# KA2_2.net
KiCad netlist of a schematic drawn in Altium Designer
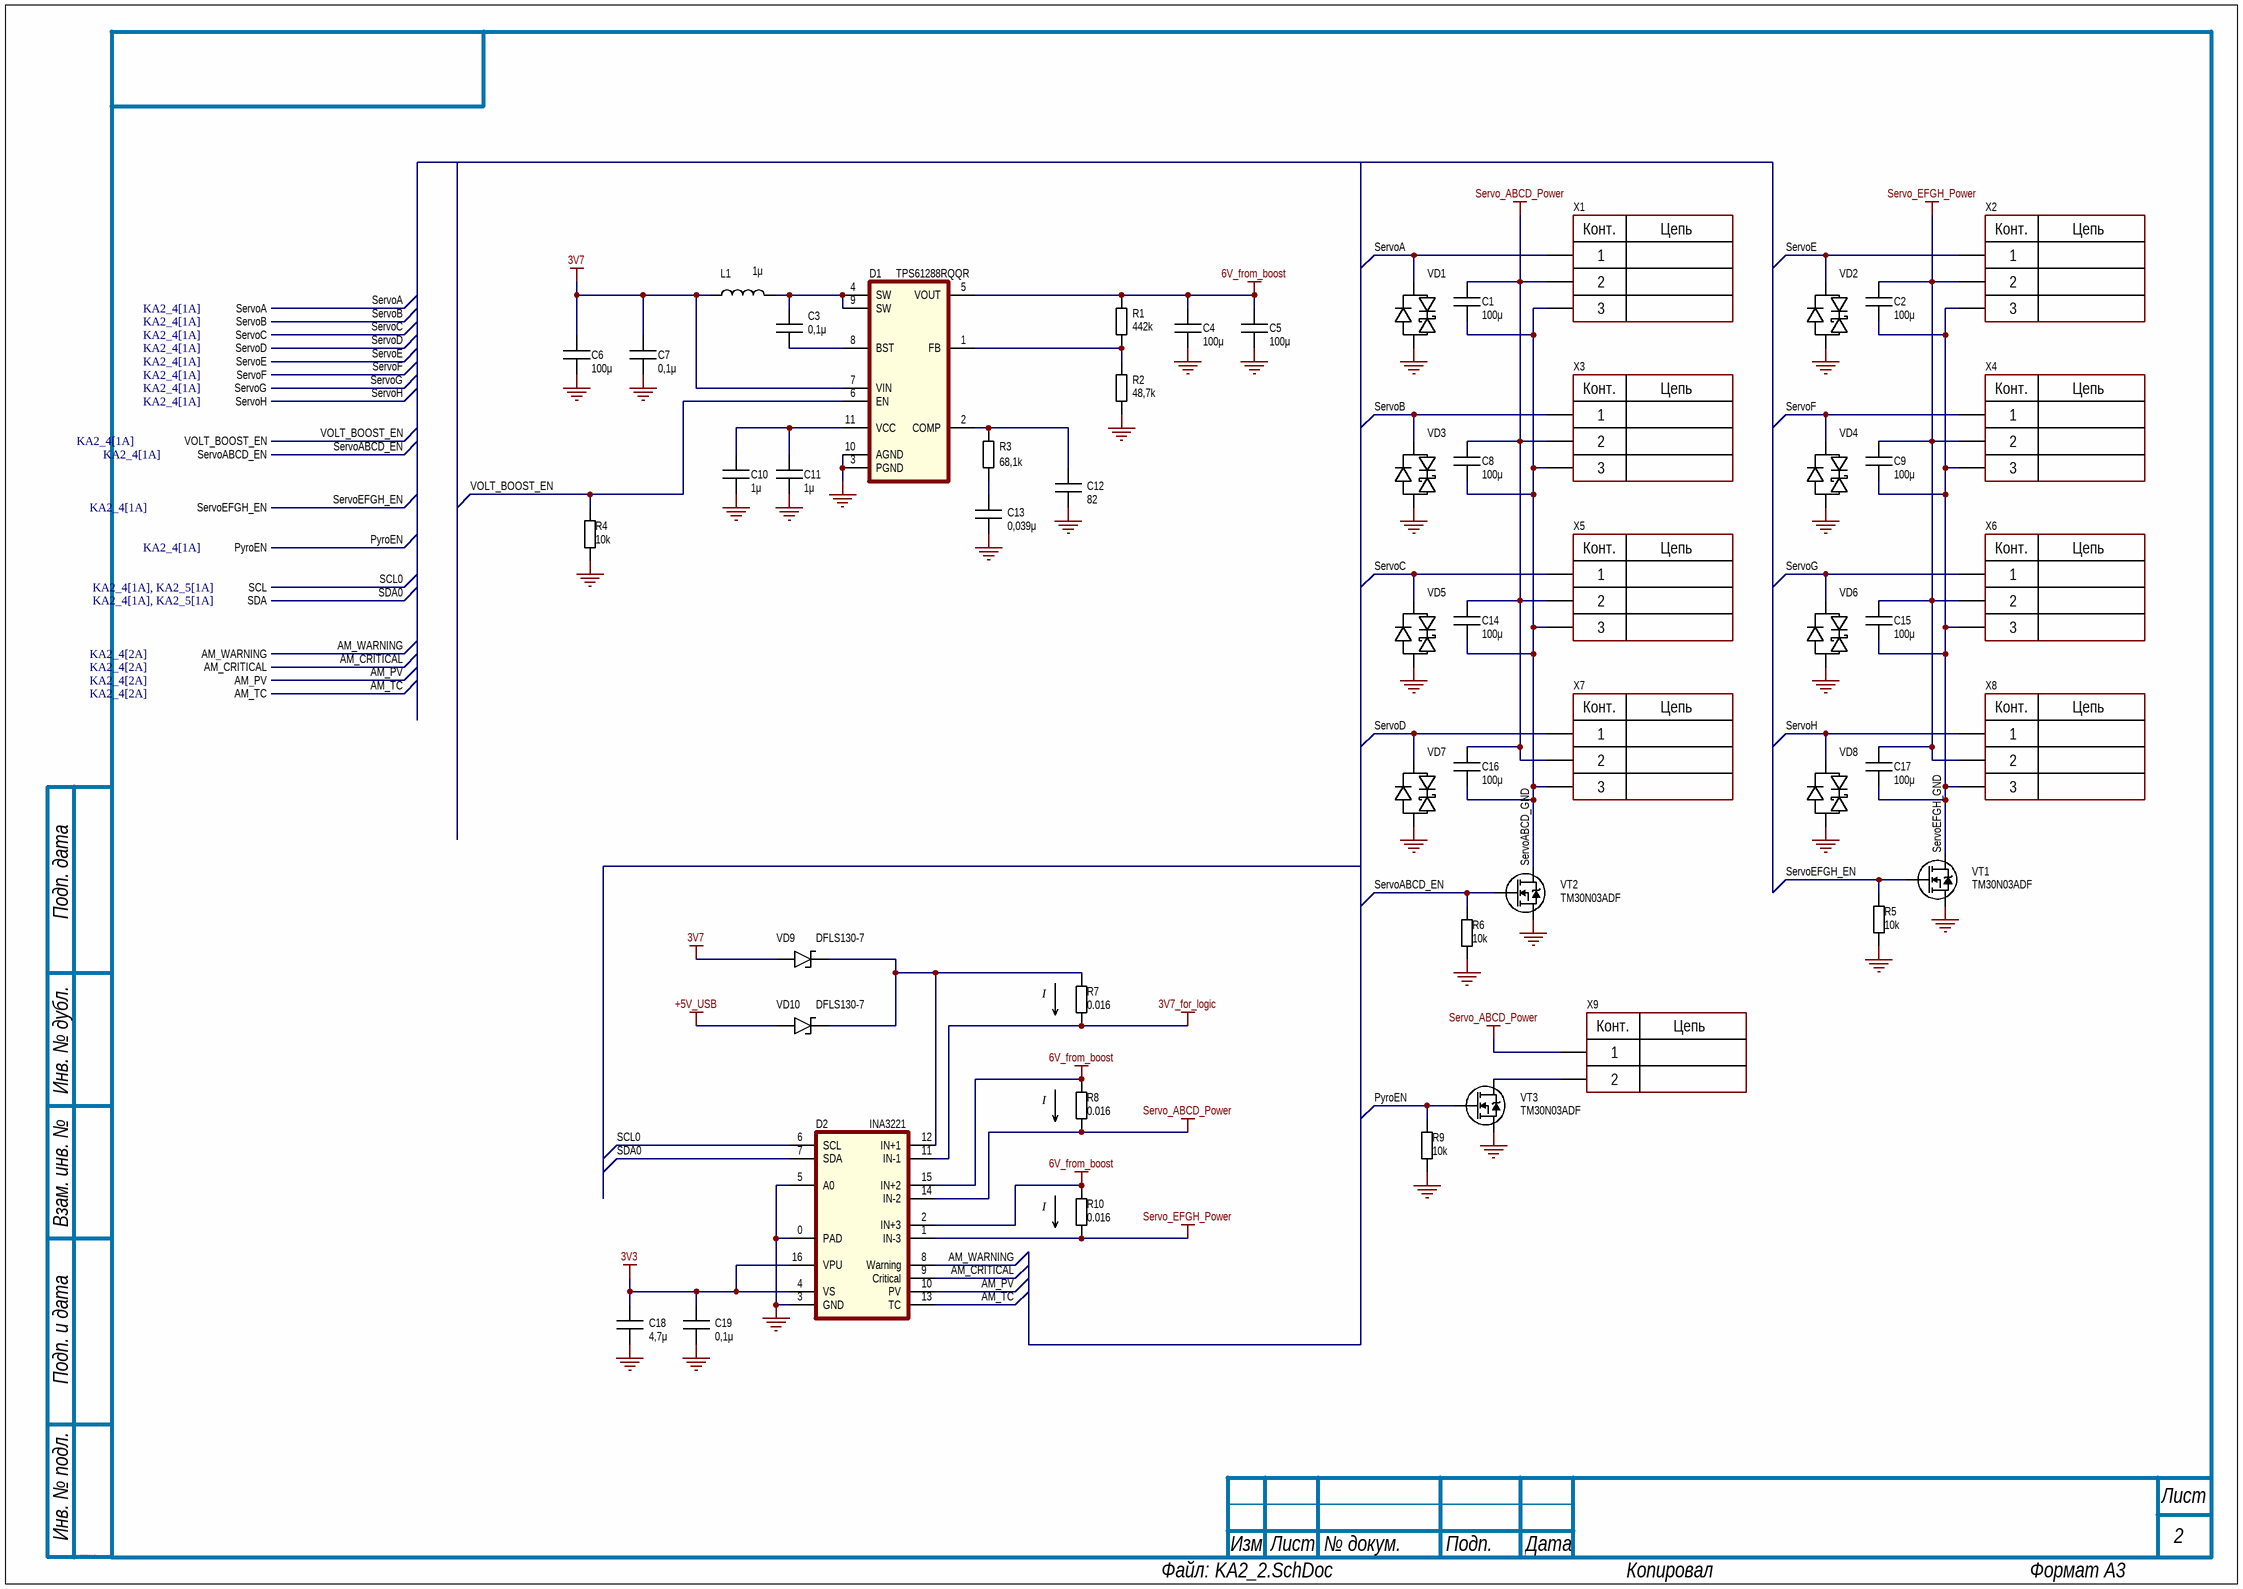
[diagram p0: KA2_2.SchDoc]

(export (version "E")
  (design (tool "Eeschema 10.0.6"))
  (components
    (comp (ref "C1")
      (value "100μ")
      (footprint "Capacitor_1206")
      (fields
        (field (name "VALUEMANUFACTURERPARTNUMBER") "Ceramic capacitor, 100μ, X7R, ±10%, 50V, 1206")
        (field (name "TOLERANCE") "±10%")
        (field (name "VOLTAGE") "50V")
      )
      (libsource (lib "Barsotion") (part "Ceramic_1206"))
    )
    (comp (ref "C2")
      (value "100μ")
      (footprint "Capacitor_1206")
      (fields
        (field (name "VALUEMANUFACTURERPARTNUMBER") "Ceramic capacitor, 100μ, X7R, ±10%, 50V, 1206")
        (field (name "TOLERANCE") "±10%")
        (field (name "VOLTAGE") "50V")
      )
      (libsource (lib "Barsotion") (part "Ceramic_1206"))
    )
    (comp (ref "C3")
      (value "0,1μ")
      (footprint "Capacitor_0402")
      (fields
        (field (name "VALUEMANUFACTURERPARTNUMBER") "Ceramic capacitor, 0,1μ, X7R, ±10%, 16V, 0402")
        (field (name "TOLERANCE") "±10%")
        (field (name "VOLTAGE") "16V")
      )
      (libsource (lib "Barsotion") (part "Ceramic_0402"))
    )
    (comp (ref "C4")
      (value "100μ")
      (footprint "Capacitor_1206")
      (fields
        (field (name "VALUEMANUFACTURERPARTNUMBER") "Ceramic capacitor, 100μ, X7R, ±10%, 50V, 1206")
        (field (name "TOLERANCE") "±10%")
        (field (name "VOLTAGE") "50V")
      )
      (libsource (lib "Barsotion") (part "Ceramic_1206"))
    )
    (comp (ref "C5")
      (value "100μ")
      (footprint "Capacitor_1206")
      (fields
        (field (name "VALUEMANUFACTURERPARTNUMBER") "Ceramic capacitor, 100μ, X7R, ±10%, 50V, 1206")
        (field (name "TOLERANCE") "±10%")
        (field (name "VOLTAGE") "50V")
      )
      (libsource (lib "Barsotion") (part "Ceramic_1206"))
    )
    (comp (ref "C6")
      (value "100μ")
      (footprint "Capacitor_1206")
      (fields
        (field (name "VALUEMANUFACTURERPARTNUMBER") "Ceramic capacitor, 100μ, X7R, ±10%, 50V, 1206")
        (field (name "TOLERANCE") "±10%")
        (field (name "VOLTAGE") "50V")
      )
      (libsource (lib "Barsotion") (part "Ceramic_1206"))
    )
    (comp (ref "C7")
      (value "0,1μ")
      (footprint "Capacitor_0402")
      (fields
        (field (name "VALUEMANUFACTURERPARTNUMBER") "Ceramic capacitor, 0,1μ, X7R, ±10%, 16V, 0402")
        (field (name "TOLERANCE") "±10%")
        (field (name "VOLTAGE") "16V")
      )
      (libsource (lib "Barsotion") (part "Ceramic_0402"))
    )
    (comp (ref "C8")
      (value "100μ")
      (footprint "Capacitor_1206")
      (fields
        (field (name "VALUEMANUFACTURERPARTNUMBER") "Ceramic capacitor, 100μ, X7R, ±10%, 50V, 1206")
        (field (name "TOLERANCE") "±10%")
        (field (name "VOLTAGE") "50V")
      )
      (libsource (lib "Barsotion") (part "Ceramic_1206"))
    )
    (comp (ref "C9")
      (value "100μ")
      (footprint "Capacitor_1206")
      (fields
        (field (name "VALUEMANUFACTURERPARTNUMBER") "Ceramic capacitor, 100μ, X7R, ±10%, 50V, 1206")
        (field (name "TOLERANCE") "±10%")
        (field (name "VOLTAGE") "50V")
      )
      (libsource (lib "Barsotion") (part "Ceramic_1206"))
    )
    (comp (ref "C10")
      (value "1μ")
      (footprint "Capacitor_0402")
      (fields
        (field (name "VALUEMANUFACTURERPARTNUMBER") "Ceramic capacitor, 1μ, X7R, ±10%, 16V, 0402")
        (field (name "TOLERANCE") "±10%")
        (field (name "VOLTAGE") "16V")
      )
      (libsource (lib "Barsotion") (part "Ceramic_0402"))
    )
    (comp (ref "C11")
      (value "1μ")
      (footprint "Capacitor_0402")
      (fields
        (field (name "VALUEMANUFACTURERPARTNUMBER") "Ceramic capacitor, 1μ, X7R, ±10%, 16V, 0402")
        (field (name "TOLERANCE") "±10%")
        (field (name "VOLTAGE") "16V")
      )
      (libsource (lib "Barsotion") (part "Ceramic_0402"))
    )
    (comp (ref "C12")
      (value "82")
      (footprint "Capacitor_0402")
      (fields
        (field (name "VALUEMANUFACTURERPARTNUMBER") "Ceramic capacitor, 82, X7R, ±10%, 16V, 0402")
        (field (name "TOLERANCE") "±10%")
        (field (name "VOLTAGE") "16V")
      )
      (libsource (lib "Barsotion") (part "Ceramic_0402"))
    )
    (comp (ref "C13")
      (value "0,039μ")
      (footprint "Capacitor_0402")
      (fields
        (field (name "VALUEMANUFACTURERPARTNUMBER") "Ceramic capacitor, 0,039μ, X7R, ±10%, 16V, 0402")
        (field (name "TOLERANCE") "±10%")
        (field (name "VOLTAGE") "16V")
      )
      (libsource (lib "Barsotion") (part "Ceramic_0402"))
    )
    (comp (ref "C14")
      (value "100μ")
      (footprint "Capacitor_1206")
      (fields
        (field (name "VALUEMANUFACTURERPARTNUMBER") "Ceramic capacitor, 100μ, X7R, ±10%, 50V, 1206")
        (field (name "TOLERANCE") "±10%")
        (field (name "VOLTAGE") "50V")
      )
      (libsource (lib "Barsotion") (part "Ceramic_1206"))
    )
    (comp (ref "C15")
      (value "100μ")
      (footprint "Capacitor_1206")
      (fields
        (field (name "VALUEMANUFACTURERPARTNUMBER") "Ceramic capacitor, 100μ, X7R, ±10%, 50V, 1206")
        (field (name "TOLERANCE") "±10%")
        (field (name "VOLTAGE") "50V")
      )
      (libsource (lib "Barsotion") (part "Ceramic_1206"))
    )
    (comp (ref "C16")
      (value "100μ")
      (footprint "Capacitor_1206")
      (fields
        (field (name "VALUEMANUFACTURERPARTNUMBER") "Ceramic capacitor, 100μ, X7R, ±10%, 50V, 1206")
        (field (name "TOLERANCE") "±10%")
        (field (name "VOLTAGE") "50V")
      )
      (libsource (lib "Barsotion") (part "Ceramic_1206"))
    )
    (comp (ref "C17")
      (value "100μ")
      (footprint "Capacitor_1206")
      (fields
        (field (name "VALUEMANUFACTURERPARTNUMBER") "Ceramic capacitor, 100μ, X7R, ±10%, 50V, 1206")
        (field (name "TOLERANCE") "±10%")
        (field (name "VOLTAGE") "50V")
      )
      (libsource (lib "Barsotion") (part "Ceramic_1206"))
    )
    (comp (ref "C18")
      (value "4,7μ")
      (footprint "Capacitor_0402")
      (fields
        (field (name "VALUEMANUFACTURERPARTNUMBER") "Ceramic capacitor, 4,7μ, X7R, ±10%, 16V, 0402")
        (field (name "TOLERANCE") "±10%")
        (field (name "VOLTAGE") "16V")
      )
      (libsource (lib "Barsotion") (part "Ceramic_0402"))
    )
    (comp (ref "C19")
      (value "0,1μ")
      (footprint "Capacitor_0402")
      (fields
        (field (name "VALUEMANUFACTURERPARTNUMBER") "Ceramic capacitor, 0,1μ, X7R, ±10%, 16V, 0402")
        (field (name "TOLERANCE") "±10%")
        (field (name "VOLTAGE") "16V")
      )
      (libsource (lib "Barsotion") (part "Ceramic_0402"))
    )
    (comp (ref "D1")
      (value "TPS61288RQQR")
      (footprint "TPS61288")
      (description "Boost Switching Regulator IC Adjustable 4.5V~18V 1 Output 15A VQFN-11-HR(2.5x3)")
      (fields (field (name "MANUFACTURER") "Texas Instruments"))
      (libsource (lib "Barsotion") (part "TPS61288RQQR"))
    )
    (comp (ref "D2")
      (value "INA3221")
      (footprint "QFN16_4x4mm")
      (description "Микросхема трехканального амперметра-вольтметра")
      (fields (field (name "MANUFACTURER") "Texas Instruments") (field (name "MFR.PART") "INA3221AIRGVR"))
      (libsource (lib "Barsotion") (part "INA3221"))
    )
    (comp (ref "L1")
      (value "1μ")
      (footprint "Inductor_AWLU0730F-1R0MGA")
      (description "17A 1uH ±20% 3.8mΩ 21A Molded Inductor SMD,7.2x7mm Fixed Inductors RoHS")
      (fields (field (name "MFR.PART") "AWLU0730F-1R0MGA") (field (name "MANUFACTURER") "APV"))
      (libsource (lib "Barsotion") (part "Inductor_AWLU0730F-1R0MGA"))
    )
    (comp (ref "R1")
      (value "442k")
      (footprint "RES: 0402")
      (fields
        (field (name "VALUEMANUFACTURERPARTNUMBER") "Resistor, 442k, ±1%, 0402")
        (field (name "TOLERANCE") "±1%")
      )
      (libsource (lib "Barsotion") (part "Resistor_0402"))
    )
    (comp (ref "R2")
      (value "48,7k")
      (footprint "RES: 0402")
      (fields
        (field (name "VALUEMANUFACTURERPARTNUMBER") "Resistor, 48,7k, ±1%, 0402")
        (field (name "TOLERANCE") "±1%")
      )
      (libsource (lib "Barsotion") (part "Resistor_0402"))
    )
    (comp (ref "R3")
      (value "68,1k")
      (footprint "RES: 0402")
      (fields
        (field (name "VALUEMANUFACTURERPARTNUMBER") "Resistor, 68,1k, ±1%, 0402")
        (field (name "TOLERANCE") "±1%")
      )
      (libsource (lib "Barsotion") (part "Resistor_0402"))
    )
    (comp (ref "R4")
      (value "10k")
      (footprint "RES: 0402")
      (fields
        (field (name "VALUEMANUFACTURERPARTNUMBER") "Resistor, 10k, ±1%, 0402")
        (field (name "TOLERANCE") "±1%")
      )
      (libsource (lib "Barsotion") (part "Resistor_0402"))
    )
    (comp (ref "R5")
      (value "10k")
      (footprint "RES: 0402")
      (fields
        (field (name "VALUEMANUFACTURERPARTNUMBER") "Resistor, 10k, ±1%, 0402")
        (field (name "TOLERANCE") "±1%")
      )
      (libsource (lib "Barsotion") (part "Resistor_0402"))
    )
    (comp (ref "R6")
      (value "10k")
      (footprint "RES: 0402")
      (fields
        (field (name "VALUEMANUFACTURERPARTNUMBER") "Resistor, 10k, ±1%, 0402")
        (field (name "TOLERANCE") "±1%")
      )
      (libsource (lib "Barsotion") (part "Resistor_0402"))
    )
    (comp (ref "R7")
      (value "0.016")
      (footprint "RES: 1206")
      (fields
        (field (name "VALUEMANUFACTURERPARTNUMBER") "Resistor, 0.016, ±1%, 1206")
        (field (name "TOLERANCE") "±1%")
      )
      (libsource (lib "Barsotion") (part "Resistor_1206"))
    )
    (comp (ref "R8")
      (value "0.016")
      (footprint "RES: 1206")
      (fields
        (field (name "VALUEMANUFACTURERPARTNUMBER") "Resistor, 0.016, ±1%, 1206")
        (field (name "TOLERANCE") "±1%")
      )
      (libsource (lib "Barsotion") (part "Resistor_1206"))
    )
    (comp (ref "R9")
      (value "10k")
      (footprint "RES: 0402")
      (fields
        (field (name "VALUEMANUFACTURERPARTNUMBER") "Resistor, 10k, ±1%, 0402")
        (field (name "TOLERANCE") "±1%")
      )
      (libsource (lib "Barsotion") (part "Resistor_0402"))
    )
    (comp (ref "R10")
      (value "0.016")
      (footprint "RES: 1206")
      (fields
        (field (name "VALUEMANUFACTURERPARTNUMBER") "Resistor, 0.016, ±1%, 1206")
        (field (name "TOLERANCE") "±1%")
      )
      (libsource (lib "Barsotion") (part "Resistor_1206"))
    )
    (comp (ref "VD1")
      (value "D1213A-01T")
      (footprint "SOD-523")
      (fields (field (name "MANUFACTURER") "Diodes") (field (name "MFR.PART") "D1213A-01T-7"))
      (libsource (lib "Barsotion") (part "D1213A-01T"))
    )
    (comp (ref "VD2")
      (value "D1213A-01T")
      (footprint "SOD-523")
      (fields (field (name "MANUFACTURER") "Diodes") (field (name "MFR.PART") "D1213A-01T-7"))
      (libsource (lib "Barsotion") (part "D1213A-01T"))
    )
    (comp (ref "VD3")
      (value "D1213A-01T")
      (footprint "SOD-523")
      (fields (field (name "MANUFACTURER") "Diodes") (field (name "MFR.PART") "D1213A-01T-7"))
      (libsource (lib "Barsotion") (part "D1213A-01T"))
    )
    (comp (ref "VD4")
      (value "D1213A-01T")
      (footprint "SOD-523")
      (fields (field (name "MANUFACTURER") "Diodes") (field (name "MFR.PART") "D1213A-01T-7"))
      (libsource (lib "Barsotion") (part "D1213A-01T"))
    )
    (comp (ref "VD5")
      (value "D1213A-01T")
      (footprint "SOD-523")
      (fields (field (name "MANUFACTURER") "Diodes") (field (name "MFR.PART") "D1213A-01T-7"))
      (libsource (lib "Barsotion") (part "D1213A-01T"))
    )
    (comp (ref "VD6")
      (value "D1213A-01T")
      (footprint "SOD-523")
      (fields (field (name "MANUFACTURER") "Diodes") (field (name "MFR.PART") "D1213A-01T-7"))
      (libsource (lib "Barsotion") (part "D1213A-01T"))
    )
    (comp (ref "VD7")
      (value "D1213A-01T")
      (footprint "SOD-523")
      (fields (field (name "MANUFACTURER") "Diodes") (field (name "MFR.PART") "D1213A-01T-7"))
      (libsource (lib "Barsotion") (part "D1213A-01T"))
    )
    (comp (ref "VD8")
      (value "D1213A-01T")
      (footprint "SOD-523")
      (fields (field (name "MANUFACTURER") "Diodes") (field (name "MFR.PART") "D1213A-01T-7"))
      (libsource (lib "Barsotion") (part "D1213A-01T"))
    )
    (comp (ref "VD9")
      (value "DFLS130-7")
      (footprint "PowerDI-123")
      (description "Диод Шоттки 30V 420mV@1A 1A PowerDI-123")
      (fields
        (field (name "MANUFACTURER") "DIODES")
        (field (name "Comment") "1 Independent 30V 420mV@1A 1A PowerDI-123 Single Diodes RoHS")
      )
      (libsource (lib "Barsotion") (part "Diode_DFLS130-7"))
    )
    (comp (ref "VD10")
      (value "DFLS130-7")
      (footprint "PowerDI-123")
      (description "Диод Шоттки 30V 420mV@1A 1A PowerDI-123")
      (fields
        (field (name "MANUFACTURER") "DIODES")
        (field (name "Comment") "1 Independent 30V 420mV@1A 1A PowerDI-123 Single Diodes RoHS")
      )
      (libsource (lib "Barsotion") (part "Diode_DFLS130-7"))
    )
    (comp (ref "VT1")
      (value "TM30N03ADF")
      (footprint "TM30N03ADF")
      (description "Транзистор N-канальный, 30В 30А 15Вт, DFN3x3-8")
      (fields (field (name "MANUFACTURER") "Tritech-MOS"))
      (libsource (lib "Barsotion") (part "TM30N03ADF"))
    )
    (comp (ref "VT2")
      (value "TM30N03ADF")
      (footprint "TM30N03ADF")
      (description "Транзистор N-канальный, 30В 30А 15Вт, DFN3x3-8")
      (fields (field (name "MANUFACTURER") "Tritech-MOS"))
      (libsource (lib "Barsotion") (part "TM30N03ADF"))
    )
    (comp (ref "VT3")
      (value "TM30N03ADF")
      (footprint "TM30N03ADF")
      (description "Транзистор N-канальный, 30В 30А 15Вт, DFN3x3-8")
      (fields (field (name "MANUFACTURER") "Tritech-MOS"))
      (libsource (lib "Barsotion") (part "TM30N03ADF"))
    )
    (comp (ref "X1")
      (value "Connector_JST_XH_B3B-XH-A_1x03_2.50mm")
      (footprint "CONN_JST_XH_B3B-XH-A_1x03_P2.50mm")
      (description "3-pin through-hole connector")
      (libsource (lib "Barsotion") (part "Connector_JST_XH_B3B-XH-A_1x03_2.50mm"))
    )
    (comp (ref "X2")
      (value "Connector_JST_XH_B3B-XH-A_1x03_2.50mm")
      (footprint "CONN_JST_XH_B3B-XH-A_1x03_P2.50mm")
      (description "3-pin through-hole connector")
      (libsource (lib "Barsotion") (part "Connector_JST_XH_B3B-XH-A_1x03_2.50mm"))
    )
    (comp (ref "X3")
      (value "Connector_JST_XH_B3B-XH-A_1x03_2.50mm")
      (footprint "CONN_JST_XH_B3B-XH-A_1x03_P2.50mm")
      (description "3-pin through-hole connector")
      (libsource (lib "Barsotion") (part "Connector_JST_XH_B3B-XH-A_1x03_2.50mm"))
    )
    (comp (ref "X4")
      (value "Connector_JST_XH_B3B-XH-A_1x03_2.50mm")
      (footprint "CONN_JST_XH_B3B-XH-A_1x03_P2.50mm")
      (description "3-pin through-hole connector")
      (libsource (lib "Barsotion") (part "Connector_JST_XH_B3B-XH-A_1x03_2.50mm"))
    )
    (comp (ref "X5")
      (value "Connector_JST_XH_B3B-XH-A_1x03_2.50mm")
      (footprint "CONN_JST_XH_B3B-XH-A_1x03_P2.50mm")
      (description "3-pin through-hole connector")
      (libsource (lib "Barsotion") (part "Connector_JST_XH_B3B-XH-A_1x03_2.50mm"))
    )
    (comp (ref "X6")
      (value "Connector_JST_XH_B3B-XH-A_1x03_2.50mm")
      (footprint "CONN_JST_XH_B3B-XH-A_1x03_P2.50mm")
      (description "3-pin through-hole connector")
      (libsource (lib "Barsotion") (part "Connector_JST_XH_B3B-XH-A_1x03_2.50mm"))
    )
    (comp (ref "X7")
      (value "Connector_JST_XH_B3B-XH-A_1x03_2.50mm")
      (footprint "CONN_JST_XH_B3B-XH-A_1x03_P2.50mm")
      (description "3-pin through-hole connector")
      (libsource (lib "Barsotion") (part "Connector_JST_XH_B3B-XH-A_1x03_2.50mm"))
    )
    (comp (ref "X8")
      (value "Connector_JST_XH_B3B-XH-A_1x03_2.50mm")
      (footprint "CONN_JST_XH_B3B-XH-A_1x03_P2.50mm")
      (description "3-pin through-hole connector")
      (libsource (lib "Barsotion") (part "Connector_JST_XH_B3B-XH-A_1x03_2.50mm"))
    )
    (comp (ref "X9")
      (value "Connector_JST_XH_B2B-XH-A_1x02_2.50mm")
      (footprint "CONN_JST_XH_B2B-XH-A_1x02_P2.50mm")
      (description "2-pin through-hole connector")
      (libsource (lib "Barsotion") (part "Connector_JST_XH_B2B-XH-A_1x02_2.50mm"))
    )
  )
  (nets
    (net (code "1") (name "+5V_USB") (class "Default")
      (node (ref "VD10") (pin "A") (pinfunction "Anode_A") (pintype "passive"))
    )
    (net (code "2") (name "/AM_CRITICAL") (class "Default")
      (node (ref "D2") (pin "9") (pinfunction "Critical_9") (pintype "passive"))
    )
    (net (code "3") (name "/AM_PV") (class "Default")
      (node (ref "D2") (pin "10") (pinfunction "PV_10") (pintype "passive"))
    )
    (net (code "4") (name "/AM_TC") (class "Default")
      (node (ref "D2") (pin "13") (pinfunction "TC_13") (pintype "passive"))
    )
    (net (code "5") (name "/AM_WARNING") (class "Default")
      (node (ref "D2") (pin "8") (pinfunction "Warning_8") (pintype "passive"))
    )
    (net (code "6") (name "/PyroEN") (class "Default")
      (node (ref "R9") (pin "2") (pinfunction "2_2") (pintype "passive"))
      (node (ref "VT3") (pin "G") (pinfunction "G_G") (pintype "passive"))
    )
    (net (code "7") (name "/SCL0") (class "Default")
      (node (ref "D2") (pin "6") (pinfunction "SCL_6") (pintype "passive"))
    )
    (net (code "8") (name "/SDA0") (class "Default")
      (node (ref "D2") (pin "7") (pinfunction "SDA_7") (pintype "passive"))
    )
    (net (code "9") (name "/ServoA") (class "Default")
      (node (ref "VD1") (pin "K") (pinfunction "K_K") (pintype "passive"))
      (node (ref "X1") (pin "1") (pinfunction "1_1") (pintype "passive"))
    )
    (net (code "10") (name "/ServoABCD_EN") (class "Default")
      (node (ref "R6") (pin "2") (pinfunction "2_2") (pintype "passive"))
      (node (ref "VT2") (pin "G") (pinfunction "G_G") (pintype "passive"))
    )
    (net (code "12") (name "/ServoABCD_GND") (class "Default")
      (node (ref "C1") (pin "1") (pinfunction "1_1") (pintype "passive"))
      (node (ref "C14") (pin "1") (pinfunction "1_1") (pintype "passive"))
      (node (ref "C16") (pin "1") (pinfunction "1_1") (pintype "passive"))
      (node (ref "C8") (pin "1") (pinfunction "1_1") (pintype "passive"))
      (node (ref "VT2") (pin "D") (pinfunction "D_D") (pintype "passive"))
      (node (ref "X1") (pin "3") (pinfunction "3_3") (pintype "passive"))
      (node (ref "X3") (pin "3") (pinfunction "3_3") (pintype "passive"))
      (node (ref "X5") (pin "3") (pinfunction "3_3") (pintype "passive"))
      (node (ref "X7") (pin "3") (pinfunction "3_3") (pintype "passive"))
    )
    (net (code "13") (name "/ServoB") (class "Default")
      (node (ref "VD3") (pin "K") (pinfunction "K_K") (pintype "passive"))
      (node (ref "X3") (pin "1") (pinfunction "1_1") (pintype "passive"))
    )
    (net (code "14") (name "/ServoC") (class "Default")
      (node (ref "VD5") (pin "K") (pinfunction "K_K") (pintype "passive"))
      (node (ref "X5") (pin "1") (pinfunction "1_1") (pintype "passive"))
    )
    (net (code "15") (name "/ServoD") (class "Default")
      (node (ref "VD7") (pin "K") (pinfunction "K_K") (pintype "passive"))
      (node (ref "X7") (pin "1") (pinfunction "1_1") (pintype "passive"))
    )
    (net (code "16") (name "/ServoE") (class "Default")
      (node (ref "VD2") (pin "K") (pinfunction "K_K") (pintype "passive"))
      (node (ref "X2") (pin "1") (pinfunction "1_1") (pintype "passive"))
    )
    (net (code "17") (name "/ServoEFGH_EN") (class "Default")
      (node (ref "R5") (pin "2") (pinfunction "2_2") (pintype "passive"))
      (node (ref "VT1") (pin "G") (pinfunction "G_G") (pintype "passive"))
    )
    (net (code "18") (name "/ServoEFGH_GND") (class "Default")
      (node (ref "C15") (pin "1") (pinfunction "1_1") (pintype "passive"))
      (node (ref "C17") (pin "1") (pinfunction "1_1") (pintype "passive"))
      (node (ref "C2") (pin "1") (pinfunction "1_1") (pintype "passive"))
      (node (ref "C9") (pin "1") (pinfunction "1_1") (pintype "passive"))
      (node (ref "VT1") (pin "D") (pinfunction "D_D") (pintype "passive"))
      (node (ref "X2") (pin "3") (pinfunction "3_3") (pintype "passive"))
      (node (ref "X4") (pin "3") (pinfunction "3_3") (pintype "passive"))
      (node (ref "X6") (pin "3") (pinfunction "3_3") (pintype "passive"))
      (node (ref "X8") (pin "3") (pinfunction "3_3") (pintype "passive"))
    )
    (net (code "19") (name "/ServoF") (class "Default")
      (node (ref "VD4") (pin "K") (pinfunction "K_K") (pintype "passive"))
      (node (ref "X4") (pin "1") (pinfunction "1_1") (pintype "passive"))
    )
    (net (code "20") (name "/ServoG") (class "Default")
      (node (ref "VD6") (pin "K") (pinfunction "K_K") (pintype "passive"))
      (node (ref "X6") (pin "1") (pinfunction "1_1") (pintype "passive"))
    )
    (net (code "21") (name "/ServoH") (class "Default")
      (node (ref "VD8") (pin "K") (pinfunction "K_K") (pintype "passive"))
      (node (ref "X8") (pin "1") (pinfunction "1_1") (pintype "passive"))
    )
    (net (code "22") (name "/VOLT_BOOST_EN") (class "Default")
      (node (ref "D1") (pin "6") (pinfunction "EN_6") (pintype "passive"))
      (node (ref "R4") (pin "2") (pinfunction "2_2") (pintype "passive"))
    )
    (net (code "23") (name "3V3") (class "Default")
      (node (ref "C18") (pin "2") (pinfunction "2_2") (pintype "passive"))
      (node (ref "C19") (pin "2") (pinfunction "2_2") (pintype "passive"))
      (node (ref "D2") (pin "16") (pinfunction "VPU_16") (pintype "passive"))
      (node (ref "D2") (pin "4") (pinfunction "VS_4") (pintype "passive"))
    )
    (net (code "24") (name "3V7") (class "Default")
      (node (ref "C6") (pin "2") (pinfunction "2_2") (pintype "passive"))
      (node (ref "C7") (pin "2") (pinfunction "2_2") (pintype "passive"))
      (node (ref "D1") (pin "7") (pinfunction "VIN_7") (pintype "passive"))
      (node (ref "L1") (pin "2") (pinfunction "2_2") (pintype "passive"))
      (node (ref "VD9") (pin "A") (pinfunction "Anode_A") (pintype "passive"))
    )
    (net (code "25") (name "3V7_for_logic") (class "Default")
      (node (ref "D2") (pin "11") (pinfunction "IN-1_11") (pintype "passive"))
      (node (ref "R7") (pin "1") (pinfunction "1_1") (pintype "passive"))
    )
    (net (code "26") (name "6V_from_boost") (class "Default")
      (node (ref "C4") (pin "2") (pinfunction "2_2") (pintype "passive"))
      (node (ref "C5") (pin "2") (pinfunction "2_2") (pintype "passive"))
      (node (ref "D1") (pin "5") (pinfunction "VOUT_5") (pintype "passive"))
      (node (ref "D2") (pin "15") (pinfunction "IN+2_15") (pintype "passive"))
      (node (ref "D2") (pin "2") (pinfunction "IN+3_2") (pintype "passive"))
      (node (ref "R1") (pin "2") (pinfunction "2_2") (pintype "passive"))
      (node (ref "R10") (pin "2") (pinfunction "2_2") (pintype "passive"))
      (node (ref "R8") (pin "2") (pinfunction "2_2") (pintype "passive"))
    )
    (net (code "27") (name "GND") (class "Default")
      (node (ref "C10") (pin "1") (pinfunction "1_1") (pintype "passive"))
      (node (ref "C11") (pin "1") (pinfunction "1_1") (pintype "passive"))
      (node (ref "C12") (pin "1") (pinfunction "1_1") (pintype "passive"))
      (node (ref "C13") (pin "1") (pinfunction "1_1") (pintype "passive"))
      (node (ref "C18") (pin "1") (pinfunction "1_1") (pintype "passive"))
      (node (ref "C19") (pin "1") (pinfunction "1_1") (pintype "passive"))
      (node (ref "C4") (pin "1") (pinfunction "1_1") (pintype "passive"))
      (node (ref "C5") (pin "1") (pinfunction "1_1") (pintype "passive"))
      (node (ref "C6") (pin "1") (pinfunction "1_1") (pintype "passive"))
      (node (ref "C7") (pin "1") (pinfunction "1_1") (pintype "passive"))
      (node (ref "D1") (pin "10") (pinfunction "AGND_10") (pintype "passive"))
      (node (ref "D1") (pin "3") (pinfunction "PGND_3") (pintype "passive"))
      (node (ref "D2") (pin "0") (pinfunction "PAD_0") (pintype "passive"))
      (node (ref "D2") (pin "3") (pinfunction "GND_3") (pintype "passive"))
      (node (ref "D2") (pin "5") (pinfunction "A0_5") (pintype "passive"))
      (node (ref "R2") (pin "1") (pinfunction "1_1") (pintype "passive"))
      (node (ref "R4") (pin "1") (pinfunction "1_1") (pintype "passive"))
      (node (ref "R5") (pin "1") (pinfunction "1_1") (pintype "passive"))
      (node (ref "R6") (pin "1") (pinfunction "1_1") (pintype "passive"))
      (node (ref "R9") (pin "1") (pinfunction "1_1") (pintype "passive"))
      (node (ref "VD1") (pin "A") (pinfunction "A_A") (pintype "passive"))
      (node (ref "VD2") (pin "A") (pinfunction "A_A") (pintype "passive"))
      (node (ref "VD3") (pin "A") (pinfunction "A_A") (pintype "passive"))
      (node (ref "VD4") (pin "A") (pinfunction "A_A") (pintype "passive"))
      (node (ref "VD5") (pin "A") (pinfunction "A_A") (pintype "passive"))
      (node (ref "VD6") (pin "A") (pinfunction "A_A") (pintype "passive"))
      (node (ref "VD7") (pin "A") (pinfunction "A_A") (pintype "passive"))
      (node (ref "VD8") (pin "A") (pinfunction "A_A") (pintype "passive"))
      (node (ref "VT1") (pin "S") (pinfunction "S_S") (pintype "passive"))
      (node (ref "VT2") (pin "S") (pinfunction "S_S") (pintype "passive"))
      (node (ref "VT3") (pin "S") (pinfunction "S_S") (pintype "passive"))
    )
    (net (code "28") (name "Net-(C3-Pad2)") (class "Default")
      (node (ref "C3") (pin "2") (pinfunction "2_2") (pintype "passive"))
      (node (ref "D1") (pin "4") (pinfunction "SW_4") (pintype "passive"))
      (node (ref "D1") (pin "9") (pinfunction "SW_9") (pintype "passive"))
      (node (ref "L1") (pin "1") (pinfunction "1_1") (pintype "passive"))
    )
    (net (code "29") (name "Net-(C13-Pad2)") (class "Default")
      (node (ref "C13") (pin "2") (pinfunction "2_2") (pintype "passive"))
      (node (ref "R3") (pin "1") (pinfunction "1_1") (pintype "passive"))
    )
    (net (code "30") (name "Net-(D1-BST)") (class "Default")
      (node (ref "C3") (pin "1") (pinfunction "1_1") (pintype "passive"))
      (node (ref "D1") (pin "8") (pinfunction "BST_8") (pintype "passive"))
    )
    (net (code "31") (name "Net-(D1-COMP)") (class "Default")
      (node (ref "C12") (pin "2") (pinfunction "2_2") (pintype "passive"))
      (node (ref "D1") (pin "2") (pinfunction "COMP_2") (pintype "passive"))
      (node (ref "R3") (pin "2") (pinfunction "2_2") (pintype "passive"))
    )
    (net (code "32") (name "Net-(D1-FB)") (class "Default")
      (node (ref "D1") (pin "1") (pinfunction "FB_1") (pintype "passive"))
      (node (ref "R1") (pin "1") (pinfunction "1_1") (pintype "passive"))
      (node (ref "R2") (pin "2") (pinfunction "2_2") (pintype "passive"))
    )
    (net (code "33") (name "Net-(D1-VCC)") (class "Default")
      (node (ref "C10") (pin "2") (pinfunction "2_2") (pintype "passive"))
      (node (ref "C11") (pin "2") (pinfunction "2_2") (pintype "passive"))
      (node (ref "D1") (pin "11") (pinfunction "VCC_11") (pintype "passive"))
    )
    (net (code "34") (name "Net-(D2-IN+1)") (class "Default")
      (node (ref "D2") (pin "12") (pinfunction "IN+1_12") (pintype "passive"))
      (node (ref "R7") (pin "2") (pinfunction "2_2") (pintype "passive"))
      (node (ref "VD10") (pin "K") (pinfunction "Kathode_K") (pintype "passive"))
      (node (ref "VD9") (pin "K") (pinfunction "Kathode_K") (pintype "passive"))
    )
    (net (code "35") (name "Net-(VT3-PadD)") (class "Default")
      (node (ref "VT3") (pin "D") (pinfunction "D_D") (pintype "passive"))
      (node (ref "X9") (pin "2") (pinfunction "2_2") (pintype "passive"))
    )
    (net (code "36") (name "Servo_ABCD_Power") (class "Default")
      (node (ref "C1") (pin "2") (pinfunction "2_2") (pintype "passive"))
      (node (ref "C14") (pin "2") (pinfunction "2_2") (pintype "passive"))
      (node (ref "C16") (pin "2") (pinfunction "2_2") (pintype "passive"))
      (node (ref "C8") (pin "2") (pinfunction "2_2") (pintype "passive"))
      (node (ref "D2") (pin "14") (pinfunction "IN-2_14") (pintype "passive"))
      (node (ref "R8") (pin "1") (pinfunction "1_1") (pintype "passive"))
      (node (ref "X1") (pin "2") (pinfunction "2_2") (pintype "passive"))
      (node (ref "X3") (pin "2") (pinfunction "2_2") (pintype "passive"))
      (node (ref "X5") (pin "2") (pinfunction "2_2") (pintype "passive"))
      (node (ref "X7") (pin "2") (pinfunction "2_2") (pintype "passive"))
      (node (ref "X9") (pin "1") (pinfunction "1_1") (pintype "passive"))
    )
    (net (code "37") (name "Servo_EFGH_Power") (class "Default")
      (node (ref "C15") (pin "2") (pinfunction "2_2") (pintype "passive"))
      (node (ref "C17") (pin "2") (pinfunction "2_2") (pintype "passive"))
      (node (ref "C2") (pin "2") (pinfunction "2_2") (pintype "passive"))
      (node (ref "C9") (pin "2") (pinfunction "2_2") (pintype "passive"))
      (node (ref "D2") (pin "1") (pinfunction "IN-3_1") (pintype "passive"))
      (node (ref "R10") (pin "1") (pinfunction "1_1") (pintype "passive"))
      (node (ref "X2") (pin "2") (pinfunction "2_2") (pintype "passive"))
      (node (ref "X4") (pin "2") (pinfunction "2_2") (pintype "passive"))
      (node (ref "X6") (pin "2") (pinfunction "2_2") (pintype "passive"))
      (node (ref "X8") (pin "2") (pinfunction "2_2") (pintype "passive"))
    )
  )
)
